# potentiometers.net
KiCad netlist of a schematic drawn in EAGLE
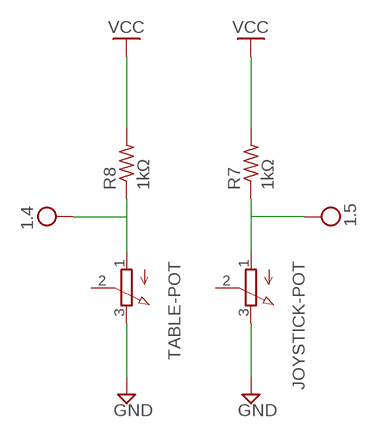
[diagram p0: schematic, sheet 1]

(export (version "E")
  (design (tool "Eeschema 10.0.6"))
  (components
    (comp (ref "JOYSTICK-POT")
      (value "3RP/1610N")
      (footprint "eagle-import:3RP_1610N")
      (libsource (lib "eagle-import") (part "3RP/1610N"))
    )
    (comp (ref "R7")
      (value "1kΩ")
      (footprint "eagle-import:0204V")
      (libsource (lib "eagle-import") (part "R-US_0204/2V"))
    )
    (comp (ref "R8")
      (value "1kΩ")
      (footprint "eagle-import:0204V")
      (libsource (lib "eagle-import") (part "R-US_0204/2V"))
    )
    (comp (ref "TABLE-POT")
      (value "3RP/1610N")
      (footprint "eagle-import:3RP_1610N")
      (libsource (lib "eagle-import") (part "3RP/1610N"))
    )
  )
  (nets
    (net (code "1") (name "1.4") (class "Default")
      (node (ref "JOYSTICK-POT") (pin "3") (pinfunction "E_3") (pintype "passive"))
      (node (ref "R7") (pin "2") (pinfunction "2_2") (pintype "passive"))
      (node (ref "R8") (pin "2") (pinfunction "2_2") (pintype "passive"))
      (node (ref "TABLE-POT") (pin "3") (pinfunction "E_3") (pintype "passive"))
    )
    (net (code "2") (name "Net-(JOYSTICK-POT-A)") (class "Default")
      (node (ref "JOYSTICK-POT") (pin "1") (pinfunction "A_1") (pintype "passive"))
      (node (ref "R7") (pin "1") (pinfunction "1_1") (pintype "passive"))
    )
    (net (code "3") (name "Net-(TABLE-POT-A)") (class "Default")
      (node (ref "R8") (pin "1") (pinfunction "1_1") (pintype "passive"))
      (node (ref "TABLE-POT") (pin "1") (pinfunction "A_1") (pintype "passive"))
    )
    (net (code "4") (name "unconnected-(JOYSTICK-POT-S-Pad2)") (class "Default")
      (node (ref "JOYSTICK-POT") (pin "2") (pinfunction "S_2") (pintype "passive"))
    )
    (net (code "5") (name "unconnected-(TABLE-POT-S-Pad2)") (class "Default")
      (node (ref "TABLE-POT") (pin "2") (pinfunction "S_2") (pintype "passive"))
    )
  )
)
